# MCP23017.net
KiCad netlist of a schematic drawn in Altium Designer
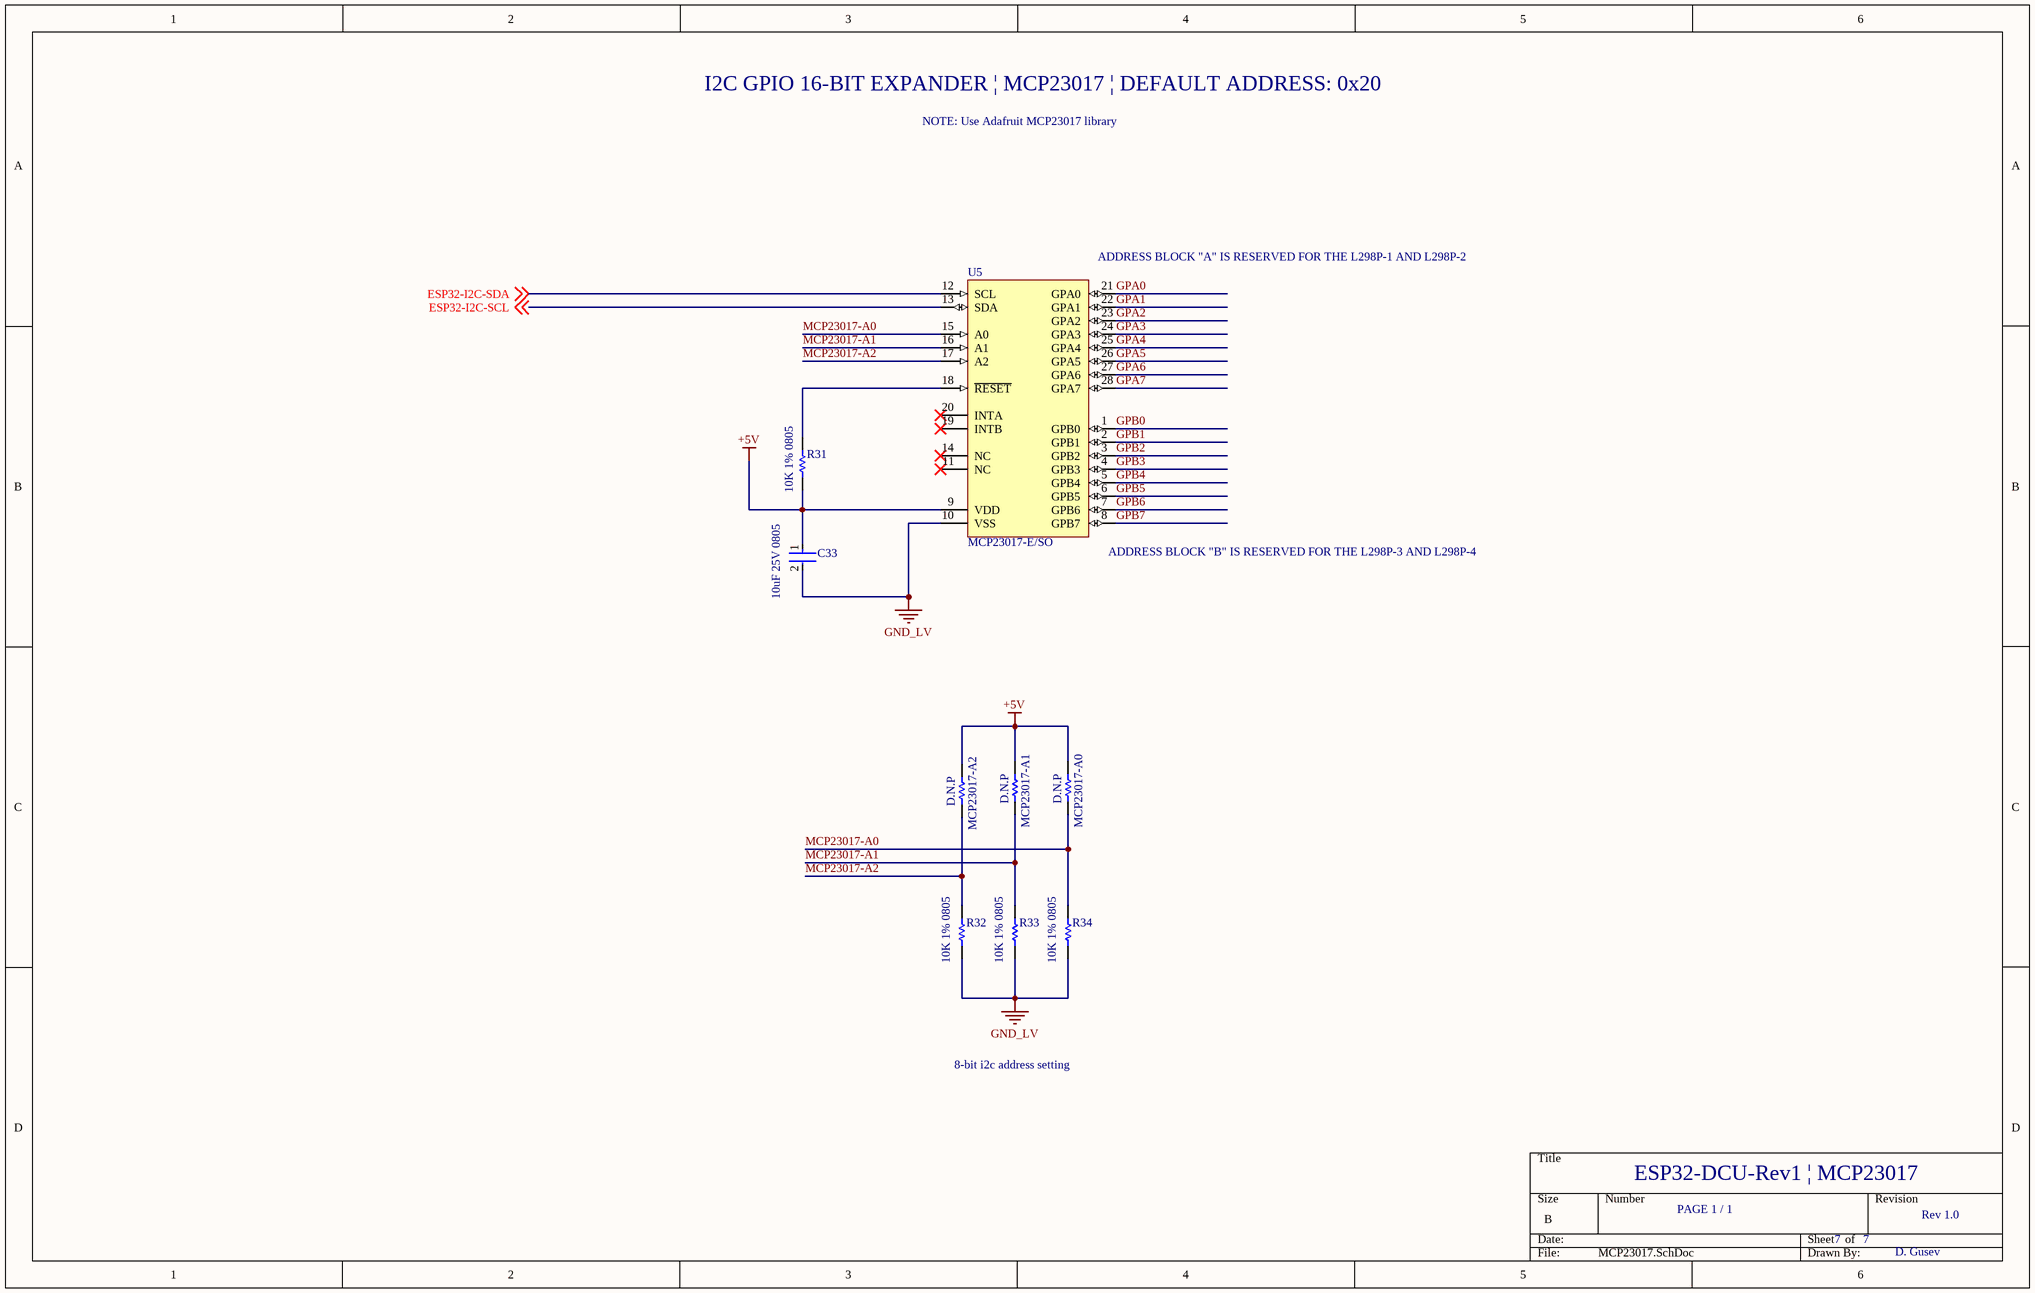
[diagram p0: MCP23017.SchDoc]

(export (version "E")
  (design (tool "Eeschema 10.0.6"))
  (components
    (comp (ref "C33")
      (value "10uF 25V 0805")
      (footprint "FP-GRM21B-0_15-IPC_B")
      (description "Chip Multilayer Ceramic Capacitors for General Purpose, 0805, 10uF, X5R, 15%, 10%, 25V")
      (fields (field (name "VOLTAGE") "25V") (field (name "TOLERANCE") "10%"))
      (libsource (lib "Altium Content Vault") (part "b4654b650e69147ec39a6b967a45e02"))
    )
    (comp (ref "MCP23017-A0")
      (value "D.N.P")
      (footprint "RESC2013X60X35LL10T20")
      (description "Chip Resistor, 1 Ohm, +/- 1%, 125 mW, -55 to 155 degC, 0805 (2012 Metric), RoHS, Tape and Reel")
      (fields (field (name "MANUFACTURER") "Yageo"))
      (libsource (lib "Altium Content Vault") (part "RES-2"))
    )
    (comp (ref "MCP23017-A1")
      (value "D.N.P")
      (footprint "RESC2013X60X35LL10T20")
      (description "Chip Resistor, 1 Ohm, +/- 1%, 125 mW, -55 to 155 degC, 0805 (2012 Metric), RoHS, Tape and Reel")
      (fields (field (name "MANUFACTURER") "Yageo"))
      (libsource (lib "Altium Content Vault") (part "RES-2"))
    )
    (comp (ref "MCP23017-A2")
      (value "D.N.P")
      (footprint "RESC2013X60X35LL10T20")
      (description "Chip Resistor, 1 Ohm, +/- 1%, 125 mW, -55 to 155 degC, 0805 (2012 Metric), RoHS, Tape and Reel")
      (fields (field (name "MANUFACTURER") "Yageo"))
      (libsource (lib "Altium Content Vault") (part "RES-2"))
    )
    (comp (ref "R31")
      (value "10K 1% 0805")
      (footprint "RESC2013X60X35ML10T20")
      (description "Chip Resistor, 10 KOhm, +/- 5%, 0.125 W, -55 to 155 degC, 0805 (2012 Metric), RoHS, Tape and Reel")
      (fields (field (name "MANUFACTURER") "Yageo"))
      (libsource (lib "Altium Content Vault") (part "RES-2"))
    )
    (comp (ref "R32")
      (value "10K 1% 0805")
      (footprint "RESC2013X60X35ML10T20")
      (description "Chip Resistor, 10 KOhm, +/- 5%, 0.125 W, -55 to 155 degC, 0805 (2012 Metric), RoHS, Tape and Reel")
      (fields (field (name "MANUFACTURER") "Yageo"))
      (libsource (lib "Altium Content Vault") (part "RES-2"))
    )
    (comp (ref "R33")
      (value "10K 1% 0805")
      (footprint "RESC2013X60X35ML10T20")
      (description "Chip Resistor, 10 KOhm, +/- 5%, 0.125 W, -55 to 155 degC, 0805 (2012 Metric), RoHS, Tape and Reel")
      (fields (field (name "MANUFACTURER") "Yageo"))
      (libsource (lib "Altium Content Vault") (part "RES-2"))
    )
    (comp (ref "R34")
      (value "10K 1% 0805")
      (footprint "RESC2013X60X35ML10T20")
      (description "Chip Resistor, 10 KOhm, +/- 5%, 0.125 W, -55 to 155 degC, 0805 (2012 Metric), RoHS, Tape and Reel")
      (fields (field (name "MANUFACTURER") "Yageo"))
      (libsource (lib "Altium Content Vault") (part "RES-2"))
    )
    (comp (ref "U5")
      (value "MCP23017-E/SO")
      (footprint "SOIC-SO28_N")
      (description "16-Bit I/O Expander with Serial Interface, 28-Pin SOIC, Extended Temperature")
      (libsource (lib "Altium Content Vault") (part "PR-BUSIC-MCP23017-28"))
    )
  )
  (nets
    (net (code "1") (name "+5V") (class "Default")
      (node (ref "C33") (pin "1") (pinfunction "1_1") (pintype "passive"))
      (node (ref "MCP23017-A0") (pin "2") (pinfunction "2_2") (pintype "passive"))
      (node (ref "MCP23017-A1") (pin "2") (pinfunction "2_2") (pintype "passive"))
      (node (ref "MCP23017-A2") (pin "2") (pinfunction "2_2") (pintype "passive"))
      (node (ref "R31") (pin "1") (pinfunction "1_1") (pintype "passive"))
      (node (ref "U5") (pin "9") (pinfunction "VDD_9") (pintype "power_in"))
    )
    (net (code "2") (name "/GPA0") (class "Default")
      (node (ref "U5") (pin "21") (pinfunction "GPA0_21") (pintype "bidirectional"))
    )
    (net (code "3") (name "/GPA1") (class "Default")
      (node (ref "U5") (pin "22") (pinfunction "GPA1_22") (pintype "bidirectional"))
    )
    (net (code "4") (name "/GPA2") (class "Default")
      (node (ref "U5") (pin "23") (pinfunction "GPA2_23") (pintype "bidirectional"))
    )
    (net (code "5") (name "/GPA3") (class "Default")
      (node (ref "U5") (pin "24") (pinfunction "GPA3_24") (pintype "bidirectional"))
    )
    (net (code "6") (name "/GPA4") (class "Default")
      (node (ref "U5") (pin "25") (pinfunction "GPA4_25") (pintype "bidirectional"))
    )
    (net (code "7") (name "/GPA5") (class "Default")
      (node (ref "U5") (pin "26") (pinfunction "GPA5_26") (pintype "bidirectional"))
    )
    (net (code "8") (name "/GPA6") (class "Default")
      (node (ref "U5") (pin "27") (pinfunction "GPA6_27") (pintype "bidirectional"))
    )
    (net (code "9") (name "/GPA7") (class "Default")
      (node (ref "U5") (pin "28") (pinfunction "GPA7_28") (pintype "bidirectional"))
    )
    (net (code "10") (name "/GPB0") (class "Default")
      (node (ref "U5") (pin "1") (pinfunction "GPB0_1") (pintype "bidirectional"))
    )
    (net (code "11") (name "/GPB1") (class "Default")
      (node (ref "U5") (pin "2") (pinfunction "GPB1_2") (pintype "bidirectional"))
    )
    (net (code "12") (name "/GPB2") (class "Default")
      (node (ref "U5") (pin "3") (pinfunction "GPB2_3") (pintype "bidirectional"))
    )
    (net (code "13") (name "/GPB3") (class "Default")
      (node (ref "U5") (pin "4") (pinfunction "GPB3_4") (pintype "bidirectional"))
    )
    (net (code "14") (name "/GPB4") (class "Default")
      (node (ref "U5") (pin "5") (pinfunction "GPB4_5") (pintype "bidirectional"))
    )
    (net (code "15") (name "/GPB5") (class "Default")
      (node (ref "U5") (pin "6") (pinfunction "GPB5_6") (pintype "bidirectional"))
    )
    (net (code "16") (name "/GPB6") (class "Default")
      (node (ref "U5") (pin "7") (pinfunction "GPB6_7") (pintype "bidirectional"))
    )
    (net (code "17") (name "/GPB7") (class "Default")
      (node (ref "U5") (pin "8") (pinfunction "GPB7_8") (pintype "bidirectional"))
    )
    (net (code "18") (name "/MCP23017-A0") (class "Default")
      (node (ref "MCP23017-A0") (pin "1") (pinfunction "1_1") (pintype "passive"))
      (node (ref "R34") (pin "1") (pinfunction "1_1") (pintype "passive"))
      (node (ref "U5") (pin "15") (pinfunction "A0_15") (pintype "input"))
    )
    (net (code "19") (name "/MCP23017-A1") (class "Default")
      (node (ref "MCP23017-A1") (pin "1") (pinfunction "1_1") (pintype "passive"))
      (node (ref "R33") (pin "1") (pinfunction "1_1") (pintype "passive"))
      (node (ref "U5") (pin "16") (pinfunction "A1_16") (pintype "input"))
    )
    (net (code "20") (name "/MCP23017-A2") (class "Default")
      (node (ref "MCP23017-A2") (pin "1") (pinfunction "1_1") (pintype "passive"))
      (node (ref "R32") (pin "1") (pinfunction "1_1") (pintype "passive"))
      (node (ref "U5") (pin "17") (pinfunction "A2_17") (pintype "input"))
    )
    (net (code "21") (name "ESP32-I2C-SCL") (class "Default")
      (node (ref "U5") (pin "13") (pinfunction "SDA_13") (pintype "bidirectional"))
    )
    (net (code "22") (name "ESP32-I2C-SDA") (class "Default")
      (node (ref "U5") (pin "12") (pinfunction "SCL_12") (pintype "input"))
    )
    (net (code "23") (name "GND_LV") (class "Default")
      (node (ref "C33") (pin "2") (pinfunction "2_2") (pintype "passive"))
      (node (ref "R32") (pin "2") (pinfunction "2_2") (pintype "passive"))
      (node (ref "R33") (pin "2") (pinfunction "2_2") (pintype "passive"))
      (node (ref "R34") (pin "2") (pinfunction "2_2") (pintype "passive"))
      (node (ref "U5") (pin "10") (pinfunction "VSS_10") (pintype "power_in"))
    )
    (net (code "24") (name "Net-(U5-~{RESET})") (class "Default")
      (node (ref "R31") (pin "2") (pinfunction "2_2") (pintype "passive"))
      (node (ref "U5") (pin "18") (pinfunction "~{RESET}_18") (pintype "input"))
    )
    (net (code "25") (name "unconnected-(U5-INTA-Pad20)") (class "Default")
      (node (ref "U5") (pin "20") (pinfunction "INTA_20") (pintype "open_collector+no_connect"))
    )
    (net (code "26") (name "unconnected-(U5-INTB-Pad19)") (class "Default")
      (node (ref "U5") (pin "19") (pinfunction "INTB_19") (pintype "open_collector+no_connect"))
    )
    (net (code "27") (name "unconnected-(U5-NC-Pad11)") (class "Default")
      (node (ref "U5") (pin "11") (pinfunction "NC_11") (pintype "passive+no_connect"))
    )
    (net (code "28") (name "unconnected-(U5-NC-Pad14)") (class "Default")
      (node (ref "U5") (pin "14") (pinfunction "NC_14") (pintype "passive+no_connect"))
    )
  )
)
